# Integrated_Main_Driver_Board-02-Sensor_C.net
KiCad netlist of a schematic drawn in Altium Designer
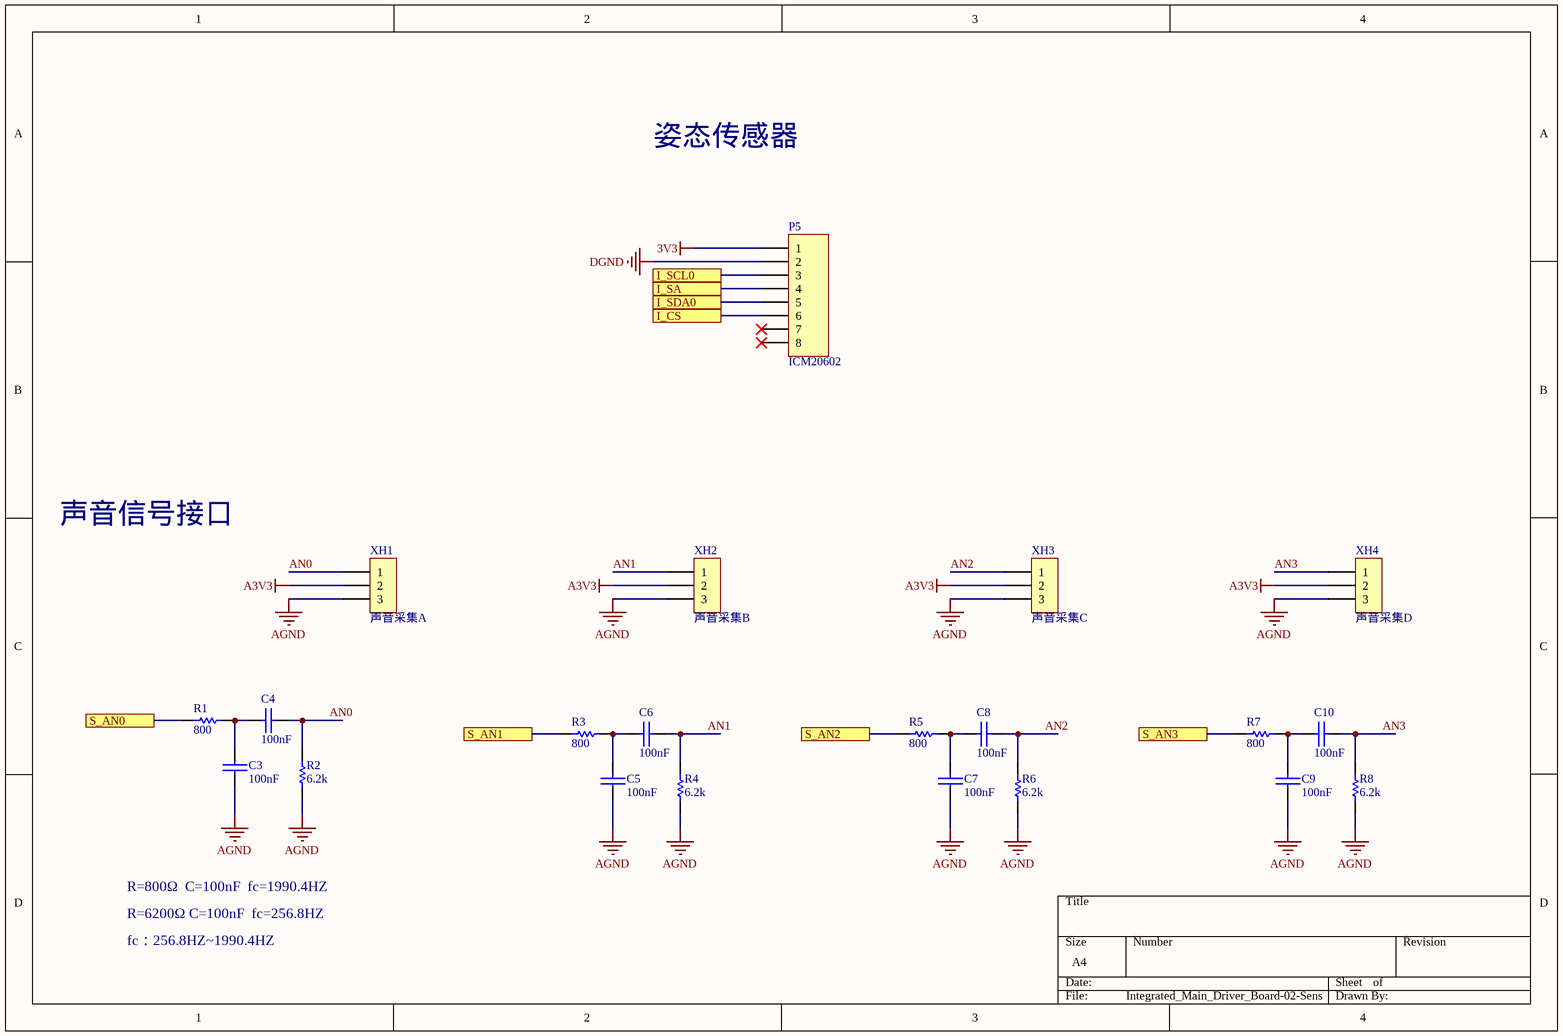
[diagram p0: Integrated_Main_Driver_Board-02-Sensor Circuit-20230110.SchDoc]

(export (version "E")
  (design (tool "Eeschema 10.0.6"))
  (components
    (comp (ref "C3")
      (value "100nF")
      (footprint "0402C")
      (description "无极性电容")
      (libsource (lib "电容") (part "CAP"))
    )
    (comp (ref "C4")
      (value "100nF")
      (footprint "0402C")
      (description "无极性电容")
      (libsource (lib "电容") (part "CAP"))
    )
    (comp (ref "C5")
      (value "100nF")
      (footprint "0402C")
      (description "无极性电容")
      (libsource (lib "电容") (part "CAP"))
    )
    (comp (ref "C6")
      (value "100nF")
      (footprint "0402C")
      (description "无极性电容")
      (libsource (lib "电容") (part "CAP"))
    )
    (comp (ref "C7")
      (value "100nF")
      (footprint "0402C")
      (description "无极性电容")
      (libsource (lib "电容") (part "CAP"))
    )
    (comp (ref "C8")
      (value "100nF")
      (footprint "0402C")
      (description "无极性电容")
      (libsource (lib "电容") (part "CAP"))
    )
    (comp (ref "C9")
      (value "100nF")
      (footprint "0402C")
      (description "无极性电容")
      (libsource (lib "电容") (part "CAP"))
    )
    (comp (ref "C10")
      (value "100nF")
      (footprint "0402C")
      (description "无极性电容")
      (libsource (lib "电容") (part "CAP"))
    )
    (comp (ref "P5")
      (value "ICM20602")
      (footprint "HDR1X8")
      (description "Header, 8-Pin")
      (fields (field (name "PUBLISHER") "Altium Limited"))
      (libsource (lib "Miscellaneous Connectors") (part "Header 8"))
    )
    (comp (ref "R1") (value "800") (footprint "0402R") (libsource (lib "电阻") (part "RES")))
    (comp (ref "R2") (value "6.2k") (footprint "0402R") (libsource (lib "电阻") (part "RES")))
    (comp (ref "R3") (value "800") (footprint "0402R") (libsource (lib "电阻") (part "RES")))
    (comp (ref "R4") (value "6.2k") (footprint "0402R") (libsource (lib "电阻") (part "RES")))
    (comp (ref "R5") (value "800") (footprint "0402R") (libsource (lib "电阻") (part "RES")))
    (comp (ref "R6") (value "6.2k") (footprint "0402R") (libsource (lib "电阻") (part "RES")))
    (comp (ref "R7") (value "800") (footprint "0402R") (libsource (lib "电阻") (part "RES")))
    (comp (ref "R8") (value "6.2k") (footprint "0402R") (libsource (lib "电阻") (part "RES")))
    (comp (ref "XH1") (value "声音采集A") (footprint "XH3/2.54mm/180") (libsource (lib "XH，VH") (part "XH3")))
    (comp (ref "XH2") (value "声音采集B") (footprint "XH3/2.54mm/180") (libsource (lib "XH，VH") (part "XH3")))
    (comp (ref "XH3") (value "声音采集C") (footprint "XH3/2.54mm/180") (libsource (lib "XH，VH") (part "XH3")))
    (comp (ref "XH4") (value "声音采集D") (footprint "XH3/2.54mm/180") (libsource (lib "XH，VH") (part "XH3")))
  )
  (nets
    (net (code "1") (name "/AN0") (class "Default")
      (node (ref "C4") (pin "1") (pinfunction "1_1") (pintype "passive"))
      (node (ref "R2") (pin "2") (pinfunction "2_2") (pintype "passive"))
      (node (ref "XH1") (pin "1") (pinfunction "1_1") (pintype "passive"))
    )
    (net (code "2") (name "/AN1") (class "Default")
      (node (ref "C6") (pin "1") (pinfunction "1_1") (pintype "passive"))
      (node (ref "R4") (pin "2") (pinfunction "2_2") (pintype "passive"))
      (node (ref "XH2") (pin "1") (pinfunction "1_1") (pintype "passive"))
    )
    (net (code "3") (name "/AN2") (class "Default")
      (node (ref "C8") (pin "1") (pinfunction "1_1") (pintype "passive"))
      (node (ref "R6") (pin "2") (pinfunction "2_2") (pintype "passive"))
      (node (ref "XH3") (pin "1") (pinfunction "1_1") (pintype "passive"))
    )
    (net (code "4") (name "/AN3") (class "Default")
      (node (ref "C10") (pin "1") (pinfunction "1_1") (pintype "passive"))
      (node (ref "R8") (pin "2") (pinfunction "2_2") (pintype "passive"))
      (node (ref "XH4") (pin "1") (pinfunction "1_1") (pintype "passive"))
    )
    (net (code "5") (name "/I_CS") (class "Default")
      (node (ref "P5") (pin "6") (pinfunction "6_6") (pintype "passive"))
    )
    (net (code "6") (name "/I_SA") (class "Default")
      (node (ref "P5") (pin "4") (pinfunction "4_4") (pintype "passive"))
    )
    (net (code "7") (name "/I_SCL0") (class "Default")
      (node (ref "P5") (pin "3") (pinfunction "3_3") (pintype "passive"))
    )
    (net (code "8") (name "/I_SDA0") (class "Default")
      (node (ref "P5") (pin "5") (pinfunction "5_5") (pintype "passive"))
    )
    (net (code "9") (name "/S_AN0") (class "Default")
      (node (ref "R1") (pin "1") (pinfunction "1_1") (pintype "passive"))
    )
    (net (code "10") (name "/S_AN1") (class "Default")
      (node (ref "R3") (pin "1") (pinfunction "1_1") (pintype "passive"))
    )
    (net (code "11") (name "/S_AN2") (class "Default")
      (node (ref "R5") (pin "1") (pinfunction "1_1") (pintype "passive"))
    )
    (net (code "12") (name "/S_AN3") (class "Default")
      (node (ref "R7") (pin "1") (pinfunction "1_1") (pintype "passive"))
    )
    (net (code "13") (name "3V3") (class "Default")
      (node (ref "P5") (pin "1") (pinfunction "1_1") (pintype "passive"))
    )
    (net (code "14") (name "A3V3") (class "Default")
      (node (ref "XH1") (pin "2") (pinfunction "2_2") (pintype "passive"))
      (node (ref "XH2") (pin "2") (pinfunction "2_2") (pintype "passive"))
      (node (ref "XH3") (pin "2") (pinfunction "2_2") (pintype "passive"))
      (node (ref "XH4") (pin "2") (pinfunction "2_2") (pintype "passive"))
    )
    (net (code "15") (name "AGND") (class "Default")
      (node (ref "C3") (pin "1") (pinfunction "1_1") (pintype "passive"))
      (node (ref "C5") (pin "1") (pinfunction "1_1") (pintype "passive"))
      (node (ref "C7") (pin "1") (pinfunction "1_1") (pintype "passive"))
      (node (ref "C9") (pin "1") (pinfunction "1_1") (pintype "passive"))
      (node (ref "R2") (pin "1") (pinfunction "1_1") (pintype "passive"))
      (node (ref "R4") (pin "1") (pinfunction "1_1") (pintype "passive"))
      (node (ref "R6") (pin "1") (pinfunction "1_1") (pintype "passive"))
      (node (ref "R8") (pin "1") (pinfunction "1_1") (pintype "passive"))
      (node (ref "XH1") (pin "3") (pinfunction "3_3") (pintype "passive"))
      (node (ref "XH2") (pin "3") (pinfunction "3_3") (pintype "passive"))
      (node (ref "XH3") (pin "3") (pinfunction "3_3") (pintype "passive"))
      (node (ref "XH4") (pin "3") (pinfunction "3_3") (pintype "passive"))
    )
    (net (code "16") (name "DGND") (class "Default")
      (node (ref "P5") (pin "2") (pinfunction "2_2") (pintype "passive"))
    )
    (net (code "17") (name "Net-(C3-Pad2)") (class "Default")
      (node (ref "C3") (pin "2") (pinfunction "2_2") (pintype "passive"))
      (node (ref "C4") (pin "2") (pinfunction "2_2") (pintype "passive"))
      (node (ref "R1") (pin "2") (pinfunction "2_2") (pintype "passive"))
    )
    (net (code "18") (name "Net-(C5-Pad2)") (class "Default")
      (node (ref "C5") (pin "2") (pinfunction "2_2") (pintype "passive"))
      (node (ref "C6") (pin "2") (pinfunction "2_2") (pintype "passive"))
      (node (ref "R3") (pin "2") (pinfunction "2_2") (pintype "passive"))
    )
    (net (code "19") (name "Net-(C7-Pad2)") (class "Default")
      (node (ref "C7") (pin "2") (pinfunction "2_2") (pintype "passive"))
      (node (ref "C8") (pin "2") (pinfunction "2_2") (pintype "passive"))
      (node (ref "R5") (pin "2") (pinfunction "2_2") (pintype "passive"))
    )
    (net (code "20") (name "Net-(C10-Pad2)") (class "Default")
      (node (ref "C10") (pin "2") (pinfunction "2_2") (pintype "passive"))
      (node (ref "C9") (pin "2") (pinfunction "2_2") (pintype "passive"))
      (node (ref "R7") (pin "2") (pinfunction "2_2") (pintype "passive"))
    )
    (net (code "21") (name "unconnected-(P5-Pad7)") (class "Default")
      (node (ref "P5") (pin "7") (pinfunction "7_7") (pintype "passive+no_connect"))
    )
    (net (code "22") (name "unconnected-(P5-Pad8)") (class "Default")
      (node (ref "P5") (pin "8") (pinfunction "8_8") (pintype "passive+no_connect"))
    )
  )
)
